# 5-channel-PWM.net
KiCad netlist of a schematic drawn in EAGLE
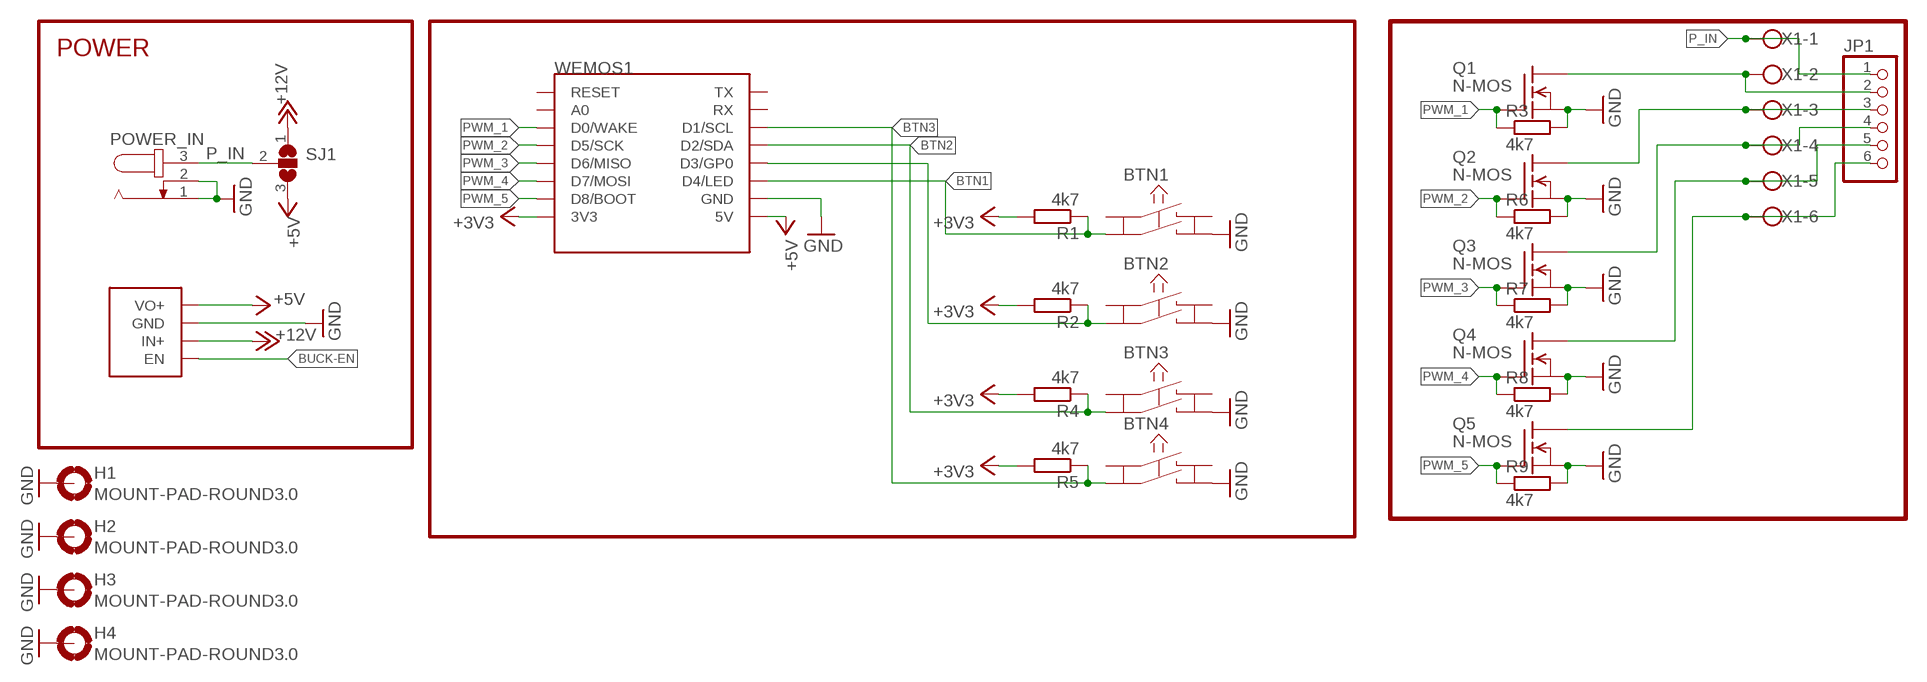
[diagram p0: schematic, sheet 1]

(export (version "E")
  (design (tool "Eeschema 10.0.6"))
  (components
    (comp (ref "BTN1")
      (value "KSM611A")
      (footprint "eagle-import:KSM611A")
      (libsource (lib "eagle-import") (part "KSM611A"))
    )
    (comp (ref "BTN2")
      (value "KSM611A")
      (footprint "eagle-import:KSM611A")
      (libsource (lib "eagle-import") (part "KSM611A"))
    )
    (comp (ref "BTN3")
      (value "KSM611A")
      (footprint "eagle-import:KSM611A")
      (libsource (lib "eagle-import") (part "KSM611A"))
    )
    (comp (ref "BTN4")
      (value "KSM611A")
      (footprint "eagle-import:KSM611A")
      (libsource (lib "eagle-import") (part "KSM611A"))
    )
    (comp (ref "H1")
      (value "MOUNT-PAD-ROUND3.0")
      (footprint "eagle-import:3,0-PAD")
      (libsource (lib "eagle-import") (part "MOUNT-PAD-ROUND3.0"))
    )
    (comp (ref "H2")
      (value "MOUNT-PAD-ROUND3.0")
      (footprint "eagle-import:3,0-PAD")
      (libsource (lib "eagle-import") (part "MOUNT-PAD-ROUND3.0"))
    )
    (comp (ref "H3")
      (value "MOUNT-PAD-ROUND3.0")
      (footprint "eagle-import:3,0-PAD")
      (libsource (lib "eagle-import") (part "MOUNT-PAD-ROUND3.0"))
    )
    (comp (ref "H4")
      (value "MOUNT-PAD-ROUND3.0")
      (footprint "eagle-import:3,0-PAD")
      (libsource (lib "eagle-import") (part "MOUNT-PAD-ROUND3.0"))
    )
    (comp (ref "JP1")
      (value "PINHD-1X06_2.54-S")
      (footprint "eagle-import:1X06-S")
      (libsource (lib "eagle-import") (part "PINHD-1X06_2.54-S"))
    )
    (comp (ref "POWER_IN")
      (value "RAPC7120")
      (footprint "eagle-import:RAPC712")
      (libsource (lib "eagle-import") (part "RAPC7120"))
    )
    (comp (ref "Q1")
      (value "N-MOS")
      (footprint "eagle-import:TO220")
      (libsource (lib "eagle-import") (part "BUZ10"))
    )
    (comp (ref "Q2")
      (value "N-MOS")
      (footprint "eagle-import:TO220")
      (libsource (lib "eagle-import") (part "BUZ10"))
    )
    (comp (ref "Q3")
      (value "N-MOS")
      (footprint "eagle-import:TO220")
      (libsource (lib "eagle-import") (part "BUZ10"))
    )
    (comp (ref "Q4")
      (value "N-MOS")
      (footprint "eagle-import:TO220")
      (libsource (lib "eagle-import") (part "BUZ10"))
    )
    (comp (ref "Q5")
      (value "N-MOS")
      (footprint "eagle-import:TO220")
      (libsource (lib "eagle-import") (part "BUZ10"))
    )
    (comp (ref "R1")
      (value "4k7")
      (footprint "eagle-import:MULTI_RESISTOR")
      (libsource (lib "eagle-import") (part "R-EU_MULTI"))
    )
    (comp (ref "R2")
      (value "4k7")
      (footprint "eagle-import:MULTI_RESISTOR")
      (libsource (lib "eagle-import") (part "R-EU_MULTI"))
    )
    (comp (ref "R3")
      (value "4k7")
      (footprint "eagle-import:MULTI_RESISTOR")
      (libsource (lib "eagle-import") (part "R-EU_MULTI"))
    )
    (comp (ref "R4")
      (value "4k7")
      (footprint "eagle-import:MULTI_RESISTOR")
      (libsource (lib "eagle-import") (part "R-EU_MULTI"))
    )
    (comp (ref "R5")
      (value "4k7")
      (footprint "eagle-import:MULTI_RESISTOR")
      (libsource (lib "eagle-import") (part "R-EU_MULTI"))
    )
    (comp (ref "R6")
      (value "4k7")
      (footprint "eagle-import:MULTI_RESISTOR")
      (libsource (lib "eagle-import") (part "R-EU_MULTI"))
    )
    (comp (ref "R7")
      (value "4k7")
      (footprint "eagle-import:MULTI_RESISTOR")
      (libsource (lib "eagle-import") (part "R-EU_MULTI"))
    )
    (comp (ref "R8")
      (value "4k7")
      (footprint "eagle-import:MULTI_RESISTOR")
      (libsource (lib "eagle-import") (part "R-EU_MULTI"))
    )
    (comp (ref "R9")
      (value "4k7")
      (footprint "eagle-import:MULTI_RESISTOR")
      (libsource (lib "eagle-import") (part "R-EU_MULTI"))
    )
    (comp (ref "SJ1")
      (value "SJ2WW")
      (footprint "eagle-import:SJ_2W")
      (libsource (lib "eagle-import") (part "SJ2WW"))
    )
    (comp (ref "U$1")
      (value "BUCK_CONVERTER_TE818")
      (footprint "eagle-import:BUCK_CONVERTER_TE818")
      (libsource (lib "eagle-import") (part "BUCK_CONVERTER_TE818"))
    )
    (comp (ref "WEMOS1")
      (value "WEMOS-D1-MINI")
      (footprint "eagle-import:WEMOS-D1-MINI")
      (libsource (lib "eagle-import") (part "WEMOS-D1-MINI"))
    )
    (comp (ref "X1")
      (value "W237-136")
      (footprint "eagle-import:W237-136")
      (fields (field (name "MPN") "237-136"))
      (libsource (lib "eagle-import") (part "W237-136"))
    )
  )
  (nets
    (net (code "1") (name "+3V3") (class "Default")
      (node (ref "R1") (pin "2@1") (pinfunction "2_2@1") (pintype "passive"))
      (node (ref "R1") (pin "2@2") (pinfunction "2_2@2") (pintype "passive"))
      (node (ref "R2") (pin "2@1") (pinfunction "2_2@1") (pintype "passive"))
      (node (ref "R2") (pin "2@2") (pinfunction "2_2@2") (pintype "passive"))
      (node (ref "R4") (pin "2@1") (pinfunction "2_2@1") (pintype "passive"))
      (node (ref "R4") (pin "2@2") (pinfunction "2_2@2") (pintype "passive"))
      (node (ref "R5") (pin "2@1") (pinfunction "2_2@1") (pintype "passive"))
      (node (ref "R5") (pin "2@2") (pinfunction "2_2@2") (pintype "passive"))
      (node (ref "WEMOS1") (pin "3V3") (pinfunction "3V3_3V3") (pintype "bidirectional"))
    )
    (net (code "2") (name "+5V") (class "Default")
      (node (ref "SJ1") (pin "3") (pinfunction "3_3") (pintype "passive"))
      (node (ref "U$1") (pin "VO+") (pinfunction "VO+_VO+") (pintype "bidirectional"))
      (node (ref "WEMOS1") (pin "5V") (pinfunction "5V_5V") (pintype "bidirectional"))
    )
    (net (code "3") (name "+12V") (class "Default")
      (node (ref "SJ1") (pin "1") (pinfunction "1_1") (pintype "passive"))
      (node (ref "U$1") (pin "IN+") (pinfunction "IN+_IN+") (pintype "bidirectional"))
    )
    (net (code "4") (name "BTN1") (class "Default")
      (node (ref "BTN1") (pin "C") (pinfunction "C_C") (pintype "passive"))
      (node (ref "R1") (pin "1@1") (pinfunction "1_1@1") (pintype "passive"))
      (node (ref "R1") (pin "1@2") (pinfunction "1_1@2") (pintype "passive"))
      (node (ref "WEMOS1") (pin "D4") (pinfunction "D4/LED_D4") (pintype "bidirectional"))
    )
    (net (code "5") (name "BTN2") (class "Default")
      (node (ref "BTN3") (pin "C") (pinfunction "C_C") (pintype "passive"))
      (node (ref "R4") (pin "1@1") (pinfunction "1_1@1") (pintype "passive"))
      (node (ref "R4") (pin "1@2") (pinfunction "1_1@2") (pintype "passive"))
      (node (ref "WEMOS1") (pin "D2") (pinfunction "D2/SDA_D2") (pintype "bidirectional"))
    )
    (net (code "6") (name "BTN3") (class "Default")
      (node (ref "BTN4") (pin "C") (pinfunction "C_C") (pintype "passive"))
      (node (ref "R5") (pin "1@1") (pinfunction "1_1@1") (pintype "passive"))
      (node (ref "R5") (pin "1@2") (pinfunction "1_1@2") (pintype "passive"))
      (node (ref "WEMOS1") (pin "D1") (pinfunction "D1/SCL_D1") (pintype "bidirectional"))
    )
    (net (code "7") (name "BUCK-EN") (class "Default")
      (node (ref "U$1") (pin "EN") (pinfunction "EN_EN") (pintype "bidirectional"))
    )
    (net (code "8") (name "GND") (class "Default")
      (node (ref "BTN1") (pin "D") (pinfunction "D_D") (pintype "passive"))
      (node (ref "BTN2") (pin "D") (pinfunction "D_D") (pintype "passive"))
      (node (ref "BTN3") (pin "D") (pinfunction "D_D") (pintype "passive"))
      (node (ref "BTN4") (pin "D") (pinfunction "D_D") (pintype "passive"))
      (node (ref "H1") (pin "B3,0") (pinfunction "MOUNT_B3,0") (pintype "passive"))
      (node (ref "H2") (pin "B3,0") (pinfunction "MOUNT_B3,0") (pintype "passive"))
      (node (ref "H3") (pin "B3,0") (pinfunction "MOUNT_B3,0") (pintype "passive"))
      (node (ref "H4") (pin "B3,0") (pinfunction "MOUNT_B3,0") (pintype "passive"))
      (node (ref "POWER_IN") (pin "1") (pinfunction "1_1") (pintype "passive"))
      (node (ref "POWER_IN") (pin "2") (pinfunction "2_2") (pintype "passive"))
      (node (ref "Q1") (pin "3") (pinfunction "S_3") (pintype "passive"))
      (node (ref "Q2") (pin "3") (pinfunction "S_3") (pintype "passive"))
      (node (ref "Q3") (pin "3") (pinfunction "S_3") (pintype "passive"))
      (node (ref "Q4") (pin "3") (pinfunction "S_3") (pintype "passive"))
      (node (ref "Q5") (pin "3") (pinfunction "S_3") (pintype "passive"))
      (node (ref "R3") (pin "2@1") (pinfunction "2_2@1") (pintype "passive"))
      (node (ref "R3") (pin "2@2") (pinfunction "2_2@2") (pintype "passive"))
      (node (ref "R6") (pin "2@1") (pinfunction "2_2@1") (pintype "passive"))
      (node (ref "R6") (pin "2@2") (pinfunction "2_2@2") (pintype "passive"))
      (node (ref "R7") (pin "2@1") (pinfunction "2_2@1") (pintype "passive"))
      (node (ref "R7") (pin "2@2") (pinfunction "2_2@2") (pintype "passive"))
      (node (ref "R8") (pin "2@1") (pinfunction "2_2@1") (pintype "passive"))
      (node (ref "R8") (pin "2@2") (pinfunction "2_2@2") (pintype "passive"))
      (node (ref "R9") (pin "2@1") (pinfunction "2_2@1") (pintype "passive"))
      (node (ref "R9") (pin "2@2") (pinfunction "2_2@2") (pintype "passive"))
      (node (ref "U$1") (pin "GND") (pinfunction "GND_GND") (pintype "bidirectional"))
      (node (ref "WEMOS1") (pin "GND") (pinfunction "GND_GND") (pintype "bidirectional"))
    )
    (net (code "9") (name "Net-(Q1-D)") (class "Default")
      (node (ref "JP1") (pin "2") (pinfunction "2_2") (pintype "passive"))
      (node (ref "Q1") (pin "2") (pinfunction "D_2") (pintype "passive"))
      (node (ref "X1") (pin "2") (pinfunction "KL_2") (pintype "passive"))
    )
    (net (code "10") (name "Net-(Q2-D)") (class "Default")
      (node (ref "JP1") (pin "3") (pinfunction "3_3") (pintype "passive"))
      (node (ref "Q2") (pin "2") (pinfunction "D_2") (pintype "passive"))
      (node (ref "X1") (pin "3") (pinfunction "KL_3") (pintype "passive"))
    )
    (net (code "11") (name "Net-(Q3-D)") (class "Default")
      (node (ref "JP1") (pin "4") (pinfunction "4_4") (pintype "passive"))
      (node (ref "Q3") (pin "2") (pinfunction "D_2") (pintype "passive"))
      (node (ref "X1") (pin "4") (pinfunction "KL_4") (pintype "passive"))
    )
    (net (code "12") (name "Net-(Q4-D)") (class "Default")
      (node (ref "JP1") (pin "5") (pinfunction "5_5") (pintype "passive"))
      (node (ref "Q4") (pin "2") (pinfunction "D_2") (pintype "passive"))
      (node (ref "X1") (pin "5") (pinfunction "KL_5") (pintype "passive"))
    )
    (net (code "13") (name "Net-(Q5-D)") (class "Default")
      (node (ref "JP1") (pin "6") (pinfunction "6_6") (pintype "passive"))
      (node (ref "Q5") (pin "2") (pinfunction "D_2") (pintype "passive"))
      (node (ref "X1") (pin "6") (pinfunction "KL_6") (pintype "passive"))
    )
    (net (code "14") (name "Net-(WEMOS1-D3{slash}GP0)") (class "Default")
      (node (ref "BTN2") (pin "C") (pinfunction "C_C") (pintype "passive"))
      (node (ref "R2") (pin "1@1") (pinfunction "1_1@1") (pintype "passive"))
      (node (ref "R2") (pin "1@2") (pinfunction "1_1@2") (pintype "passive"))
      (node (ref "WEMOS1") (pin "D3") (pinfunction "D3/GP0_D3") (pintype "bidirectional"))
    )
    (net (code "15") (name "PWM_1") (class "Default")
      (node (ref "Q1") (pin "1") (pinfunction "G_1") (pintype "passive"))
      (node (ref "R3") (pin "1@1") (pinfunction "1_1@1") (pintype "passive"))
      (node (ref "R3") (pin "1@2") (pinfunction "1_1@2") (pintype "passive"))
      (node (ref "WEMOS1") (pin "D0") (pinfunction "D0/WAKE_D0") (pintype "bidirectional"))
    )
    (net (code "16") (name "PWM_2") (class "Default")
      (node (ref "Q2") (pin "1") (pinfunction "G_1") (pintype "passive"))
      (node (ref "R6") (pin "1@1") (pinfunction "1_1@1") (pintype "passive"))
      (node (ref "R6") (pin "1@2") (pinfunction "1_1@2") (pintype "passive"))
      (node (ref "WEMOS1") (pin "D5") (pinfunction "D5/SCK_D5") (pintype "bidirectional"))
    )
    (net (code "17") (name "PWM_3") (class "Default")
      (node (ref "Q3") (pin "1") (pinfunction "G_1") (pintype "passive"))
      (node (ref "R7") (pin "1@1") (pinfunction "1_1@1") (pintype "passive"))
      (node (ref "R7") (pin "1@2") (pinfunction "1_1@2") (pintype "passive"))
      (node (ref "WEMOS1") (pin "D6") (pinfunction "D6/MISO_D6") (pintype "bidirectional"))
    )
    (net (code "18") (name "PWM_4") (class "Default")
      (node (ref "Q4") (pin "1") (pinfunction "G_1") (pintype "passive"))
      (node (ref "R8") (pin "1@1") (pinfunction "1_1@1") (pintype "passive"))
      (node (ref "R8") (pin "1@2") (pinfunction "1_1@2") (pintype "passive"))
      (node (ref "WEMOS1") (pin "D7") (pinfunction "D7/MOSI_D7") (pintype "bidirectional"))
    )
    (net (code "19") (name "PWM_5") (class "Default")
      (node (ref "Q5") (pin "1") (pinfunction "G_1") (pintype "passive"))
      (node (ref "R9") (pin "1@1") (pinfunction "1_1@1") (pintype "passive"))
      (node (ref "R9") (pin "1@2") (pinfunction "1_1@2") (pintype "passive"))
      (node (ref "WEMOS1") (pin "D8") (pinfunction "D8/BOOT_D8") (pintype "bidirectional"))
    )
    (net (code "20") (name "P_IN") (class "Default")
      (node (ref "JP1") (pin "1") (pinfunction "1_1") (pintype "passive"))
      (node (ref "POWER_IN") (pin "3") (pinfunction "3_3") (pintype "passive"))
      (node (ref "SJ1") (pin "2") (pinfunction "2_2") (pintype "passive"))
      (node (ref "X1") (pin "1") (pinfunction "KL_1") (pintype "passive"))
    )
    (net (code "21") (name "unconnected-(BTN1-PadA)") (class "Default")
      (node (ref "BTN1") (pin "A") (pinfunction "A_A") (pintype "passive"))
    )
    (net (code "22") (name "unconnected-(BTN1-PadB)") (class "Default")
      (node (ref "BTN1") (pin "B") (pinfunction "B_B") (pintype "passive"))
    )
    (net (code "23") (name "unconnected-(BTN2-PadA)") (class "Default")
      (node (ref "BTN2") (pin "A") (pinfunction "A_A") (pintype "passive"))
    )
    (net (code "24") (name "unconnected-(BTN2-PadB)") (class "Default")
      (node (ref "BTN2") (pin "B") (pinfunction "B_B") (pintype "passive"))
    )
    (net (code "25") (name "unconnected-(BTN3-PadA)") (class "Default")
      (node (ref "BTN3") (pin "A") (pinfunction "A_A") (pintype "passive"))
    )
    (net (code "26") (name "unconnected-(BTN3-PadB)") (class "Default")
      (node (ref "BTN3") (pin "B") (pinfunction "B_B") (pintype "passive"))
    )
    (net (code "27") (name "unconnected-(BTN4-PadA)") (class "Default")
      (node (ref "BTN4") (pin "A") (pinfunction "A_A") (pintype "passive"))
    )
    (net (code "28") (name "unconnected-(BTN4-PadB)") (class "Default")
      (node (ref "BTN4") (pin "B") (pinfunction "B_B") (pintype "passive"))
    )
    (net (code "29") (name "unconnected-(WEMOS1-PadA0)") (class "Default")
      (node (ref "WEMOS1") (pin "A0") (pinfunction "A0_A0") (pintype "bidirectional"))
    )
    (net (code "30") (name "unconnected-(WEMOS1-PadRESET)") (class "Default")
      (node (ref "WEMOS1") (pin "RESET") (pinfunction "RESET_RESET") (pintype "bidirectional"))
    )
    (net (code "31") (name "unconnected-(WEMOS1-PadRX)") (class "Default")
      (node (ref "WEMOS1") (pin "RX") (pinfunction "RX_RX") (pintype "bidirectional"))
    )
    (net (code "32") (name "unconnected-(WEMOS1-PadTX)") (class "Default")
      (node (ref "WEMOS1") (pin "TX") (pinfunction "TX_TX") (pintype "bidirectional"))
    )
  )
)
